# Power.net
KiCad netlist of a schematic drawn in Altium Designer
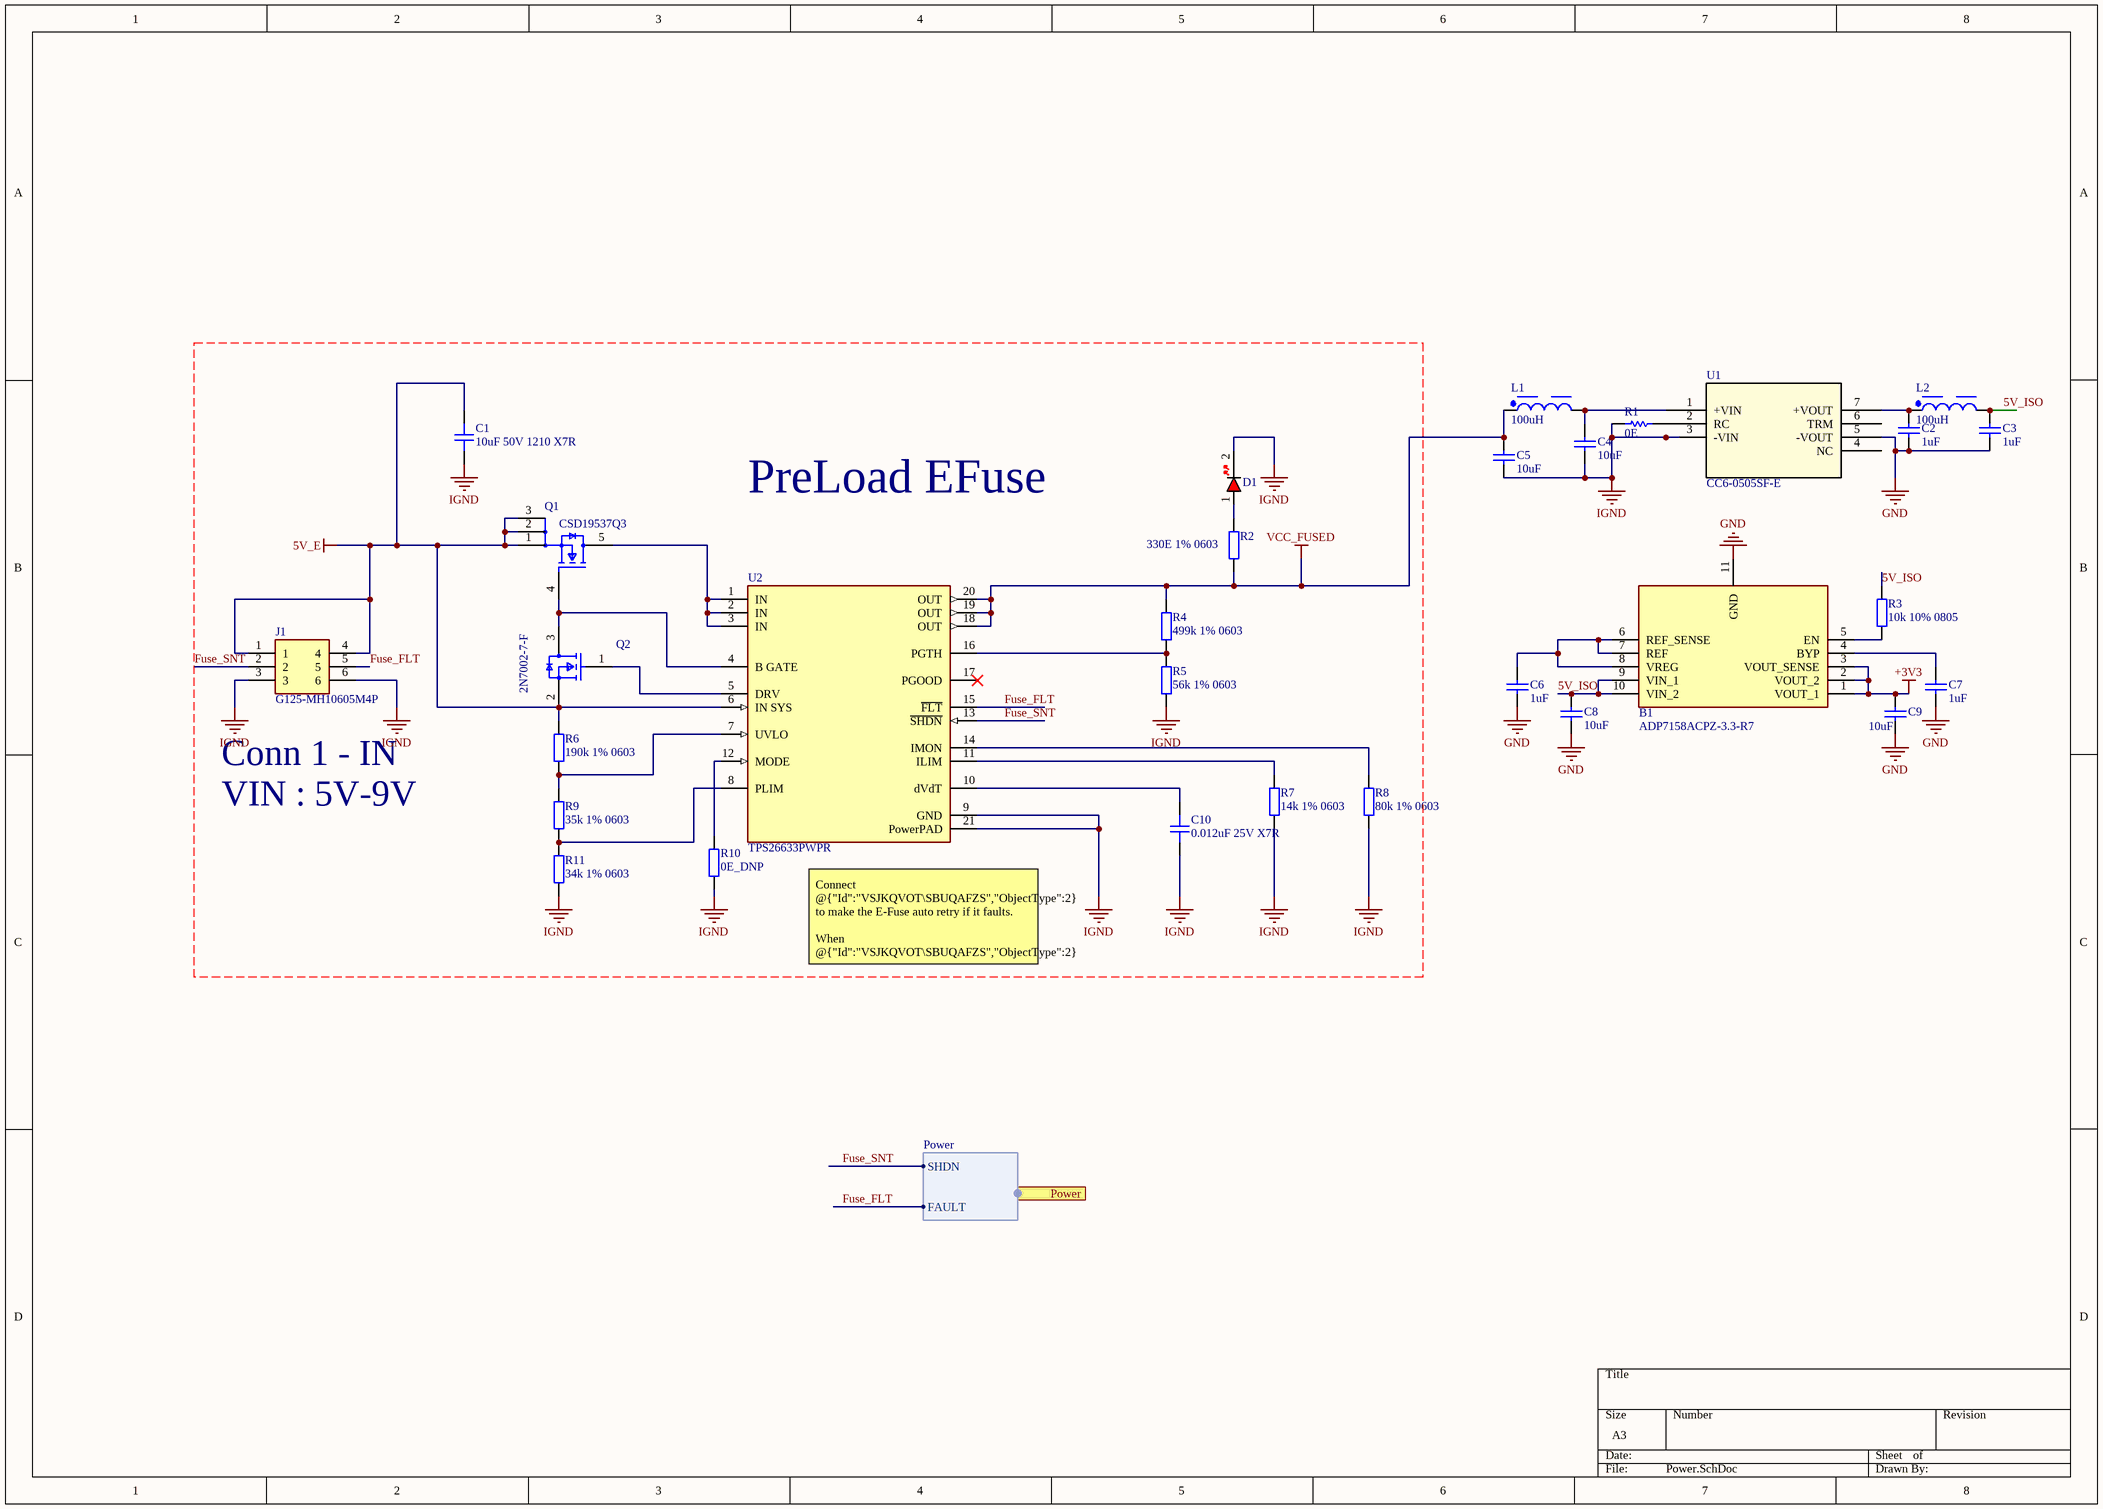
[diagram p0: Power.SchDoc]

(export (version "E")
  (design (tool "Eeschema 10.0.6"))
  (components
    (comp (ref "B1")
      (value "ADP7158ACPZ-3.3-R7")
      (footprint "LFCSP -10")
      (description "LDO Voltage Regulators 3.3/5Vin 2A Ultra Low Noise LDO Fixed")
      (fields (field (name "MOUSER PART NUMBER") "584-ADP7158ACPZ3.3R7"))
      (libsource (lib "ADP7158ACPZ-3.3-R7") (part "ADP7158ACPZ-3.3-R7"))
    )
    (comp (ref "C1")
      (value "10uF 50V 1210 X7R")
      (footprint "CAP1210S")
      (description "Capacitor SMD 1210")
      (libsource (lib "Schematic-Lib-PhilsLab") (part "CAP_1210"))
    )
    (comp (ref "C2")
      (value "1uF")
      (footprint "CAP0603S")
      (description "Capacitor")
      (fields (field (name "PUBLISHER") "Altium Limited"))
      (libsource (lib "Miscellaneous Devices") (part "CAP"))
    )
    (comp (ref "C3")
      (value "1uF")
      (footprint "CAP0603S")
      (description "Capacitor")
      (fields (field (name "PUBLISHER") "Altium Limited"))
      (libsource (lib "Miscellaneous Devices") (part "CAP"))
    )
    (comp (ref "C4")
      (value "10uF")
      (footprint "CAP0603S")
      (description "Capacitor")
      (fields (field (name "PUBLISHER") "Altium Limited"))
      (libsource (lib "Miscellaneous Devices") (part "CAP"))
    )
    (comp (ref "C5")
      (value "10uF")
      (footprint "CAP0603S")
      (description "Capacitor")
      (fields (field (name "PUBLISHER") "Altium Limited"))
      (libsource (lib "Miscellaneous Devices") (part "CAP"))
    )
    (comp (ref "C6")
      (value "1uF")
      (footprint "CAP0603S")
      (description "Capacitor")
      (fields (field (name "PUBLISHER") "Altium Limited"))
      (libsource (lib "Miscellaneous Devices") (part "CAP"))
    )
    (comp (ref "C7")
      (value "1uF")
      (footprint "CAP0603S")
      (description "Capacitor")
      (fields (field (name "PUBLISHER") "Altium Limited"))
      (libsource (lib "Miscellaneous Devices") (part "CAP"))
    )
    (comp (ref "C8")
      (value "10uF")
      (footprint "CAP0603S")
      (description "Capacitor")
      (fields (field (name "PUBLISHER") "Altium Limited"))
      (libsource (lib "Miscellaneous Devices") (part "CAP"))
    )
    (comp (ref "C9")
      (value "10uF")
      (footprint "CAP0603S")
      (description "Capacitor")
      (fields (field (name "PUBLISHER") "Altium Limited"))
      (libsource (lib "Miscellaneous Devices") (part "CAP"))
    )
    (comp (ref "C10")
      (value "0.012uF 25V X7R")
      (footprint "CAP0805S")
      (description "Capacitor SMD 0603")
      (libsource (lib "Schematic-Lib-PhilsLab") (part "CAP_0603"))
    )
    (comp (ref "D1")
      (value "RED")
      (footprint "LED 0603_RED")
      (description "LED 0603 RED SMD")
      (libsource (lib "Schematic-Lib-PhilsLab") (part "LED_0603_RED"))
    )
    (comp (ref "J1")
      (value "G125-MH10605M4P")
      (footprint "HARWIN_G125-MH10605M4P")
      (description "Connector")
      (fields (field (name "MOUSER PART NUMBER") "855-G125MH1065M4PM4P"))
      (libsource (lib "SamacSys") (part "G125-MH10605M4P"))
    )
    (comp (ref "L1")
      (value "100uH")
      (footprint "IND_SEMI_SHIELD_6.0X6.0_H4.5_SMD")
      (fields (field (name "TOLERANCE") "20%"))
      (libsource (lib "TMTC_Board") (part "CMP-1396-00036-2"))
    )
    (comp (ref "L2")
      (value "100uH")
      (footprint "IND_SEMI_SHIELD_6.0X6.0_H4.5_SMD")
      (fields (field (name "TOLERANCE") "20%"))
      (libsource (lib "TMTC_Board") (part "CMP-1396-00036-2"))
    )
    (comp (ref "Q1")
      (value "CSD19537Q3")
      (footprint "TRANS_CSD19537Q3")
      (description "MOSFET N-CH 100V 50A 8VSON")
      (libsource (lib "Miscellaneous Devices") (part "7382af88e928fdc71488234cfaaf11c"))
    )
    (comp (ref "Q2")
      (value "2N7002-7-F")
      (footprint "SOT23_3")
      (description "MOSFET N-CH 60V 115MA SOT23-3")
      (fields (field (name "VOLTAGE") "60V"))
      (libsource (lib "Miscellaneous Devices") (part "3b9c635fedb024a5347a57b145af9cc"))
    )
    (comp (ref "R1")
      (value "0E")
      (footprint "RES0402S")
      (description "Resistor")
      (fields (field (name "PUBLISHER") "Altium Limited"))
      (libsource (lib "Miscellaneous Devices") (part "res1"))
    )
    (comp (ref "R2")
      (value "330E 1% 0603")
      (footprint "RES0603S")
      (description "Resistor SMD 0603")
      (libsource (lib "Schematic-Lib-PhilsLab") (part "RES_0603"))
    )
    (comp (ref "R3")
      (value "10k 10% 0805")
      (footprint "RES0805S")
      (description "Resistor SMD 0805")
      (libsource (lib "Schematic-Lib-PhilsLab") (part "RES_0805"))
    )
    (comp (ref "R4")
      (value "499k 1% 0603")
      (footprint "RES0603S")
      (description "Resistor SMD 0603")
      (libsource (lib "Schematic-Lib-PhilsLab") (part "RES_0603"))
    )
    (comp (ref "R5")
      (value "56k 1% 0603")
      (footprint "RES0603S")
      (description "Resistor SMD 0603")
      (libsource (lib "Schematic-Lib-PhilsLab") (part "RES_0603"))
    )
    (comp (ref "R6")
      (value "190k 1% 0603")
      (footprint "RES0603S")
      (description "Resistor SMD 0603")
      (libsource (lib "Schematic-Lib-PhilsLab") (part "RES_0603"))
    )
    (comp (ref "R7")
      (value "14k 1% 0603")
      (footprint "RES0603S")
      (description "Resistor SMD 0603")
      (libsource (lib "Schematic-Lib-PhilsLab") (part "RES_0603"))
    )
    (comp (ref "R8")
      (value "80k 1% 0603")
      (footprint "RES0402S")
      (description "Resistor SMD 0603")
      (libsource (lib "Schematic-Lib-PhilsLab") (part "RES_0603"))
    )
    (comp (ref "R9")
      (value "35k 1% 0603")
      (footprint "RES0603S")
      (description "Resistor SMD 0603")
      (libsource (lib "Schematic-Lib-PhilsLab") (part "RES_0603"))
    )
    (comp (ref "R10")
      (value "0E_DNP")
      (footprint "RES0603S")
      (description "Resistor SMD 0603")
      (libsource (lib "Schematic-Lib-PhilsLab") (part "RES_0603"))
    )
    (comp (ref "R11")
      (value "34k 1% 0603")
      (footprint "RES0603S")
      (description "Resistor SMD 0603")
      (libsource (lib "Schematic-Lib-PhilsLab") (part "RES_0603"))
    )
    (comp (ref "U1")
      (value "CC6-0505SF-E")
      (footprint "CONV_CC6-0505SF-E")
      (description "No Description Available")
      (libsource (lib "CC6-0505SF-E") (part "CC6-0505SF-E"))
    )
    (comp (ref "U2")
      (value "TPS26633PWPR")
      (footprint "SOP65P640X110-21N")
      (description "4.5V - 60V 6A 29MOHM EFUSE")
      (libsource (lib "Miscellaneous Devices") (part "3aa6c8470eea581a3a5f71473fd1f1f"))
    )
  )
  (nets
    (net (code "2") (name "+3V3") (class "Default")
      (node (ref "B1") (pin "1") (pinfunction "VOUT_1_1") (pintype "passive"))
      (node (ref "B1") (pin "2") (pinfunction "VOUT_2_2") (pintype "passive"))
      (node (ref "B1") (pin "3") (pinfunction "VOUT_SENSE_3") (pintype "passive"))
      (node (ref "C9") (pin "1") (pinfunction "1_1") (pintype "passive"))
    )
    (net (code "3") (name "/5V_ISO") (class "Default")
      (node (ref "B1") (pin "10") (pinfunction "VIN_2_10") (pintype "passive"))
      (node (ref "B1") (pin "9") (pinfunction "VIN_1_9") (pintype "passive"))
      (node (ref "C3") (pin "1") (pinfunction "1_1") (pintype "passive"))
      (node (ref "C8") (pin "1") (pinfunction "1_1") (pintype "passive"))
      (node (ref "L2") (pin "2") (pinfunction "2_2") (pintype "passive"))
      (node (ref "R3") (pin "1") (pinfunction "1_1") (pintype "passive"))
    )
    (net (code "4") (name "/Fuse_FLT") (class "Default")
      (node (ref "J1") (pin "5") (pinfunction "5_5") (pintype "passive"))
      (node (ref "U2") (pin "15") (pinfunction "~{FLT}_15") (pintype "passive"))
    )
    (net (code "5") (name "/Fuse_SNT") (class "Default")
      (node (ref "J1") (pin "2") (pinfunction "2_2") (pintype "passive"))
      (node (ref "U2") (pin "13") (pinfunction "~{SHDN}_13") (pintype "input"))
    )
    (net (code "7") (name "5V_E") (class "Default")
      (node (ref "C1") (pin "2") (pinfunction "2_2") (pintype "passive"))
      (node (ref "J1") (pin "1") (pinfunction "1_1") (pintype "passive"))
      (node (ref "J1") (pin "4") (pinfunction "4_4") (pintype "passive"))
      (node (ref "Q1") (pin "1") (pinfunction "S_1") (pintype "passive"))
      (node (ref "Q1") (pin "2") (pinfunction "S_2") (pintype "passive"))
      (node (ref "Q1") (pin "3") (pinfunction "S_3") (pintype "passive"))
      (node (ref "Q2") (pin "2") (pinfunction "S_2") (pintype "passive"))
      (node (ref "R6") (pin "2") (pinfunction "2_2") (pintype "passive"))
      (node (ref "U2") (pin "6") (pinfunction "IN_SYS_6") (pintype "input"))
    )
    (net (code "8") (name "GND") (class "Default")
      (node (ref "B1") (pin "11") (pinfunction "GND_11") (pintype "passive"))
      (node (ref "C2") (pin "2") (pinfunction "2_2") (pintype "passive"))
      (node (ref "C3") (pin "2") (pinfunction "2_2") (pintype "passive"))
      (node (ref "C6") (pin "2") (pinfunction "2_2") (pintype "passive"))
      (node (ref "C7") (pin "2") (pinfunction "2_2") (pintype "passive"))
      (node (ref "C8") (pin "2") (pinfunction "2_2") (pintype "passive"))
      (node (ref "C9") (pin "2") (pinfunction "2_2") (pintype "passive"))
      (node (ref "U1") (pin "5") (pinfunction "-VOUT_5") (pintype "passive"))
    )
    (net (code "9") (name "IGND") (class "Default")
      (node (ref "C1") (pin "1") (pinfunction "1_1") (pintype "passive"))
      (node (ref "C10") (pin "1") (pinfunction "1_1") (pintype "passive"))
      (node (ref "C4") (pin "2") (pinfunction "2_2") (pintype "passive"))
      (node (ref "C5") (pin "2") (pinfunction "2_2") (pintype "passive"))
      (node (ref "D1") (pin "2") (pinfunction "K_2") (pintype "passive"))
      (node (ref "J1") (pin "3") (pinfunction "3_3") (pintype "passive"))
      (node (ref "J1") (pin "6") (pinfunction "6_6") (pintype "passive"))
      (node (ref "R1") (pin "1") (pinfunction "1_1") (pintype "passive"))
      (node (ref "R10") (pin "1") (pinfunction "1_1") (pintype "passive"))
      (node (ref "R11") (pin "1") (pinfunction "1_1") (pintype "passive"))
      (node (ref "R5") (pin "1") (pinfunction "1_1") (pintype "passive"))
      (node (ref "R7") (pin "1") (pinfunction "1_1") (pintype "passive"))
      (node (ref "R8") (pin "1") (pinfunction "1_1") (pintype "passive"))
      (node (ref "U1") (pin "3") (pinfunction "-VIN_3") (pintype "power_in"))
      (node (ref "U2") (pin "21") (pinfunction "PowerPAD_21") (pintype "power_in"))
      (node (ref "U2") (pin "9") (pinfunction "GND_9") (pintype "power_in"))
    )
    (net (code "10") (name "Net-(B1-BYP)") (class "Default")
      (node (ref "B1") (pin "4") (pinfunction "BYP_4") (pintype "passive"))
      (node (ref "C7") (pin "1") (pinfunction "1_1") (pintype "passive"))
    )
    (net (code "11") (name "Net-(B1-EN)") (class "Default")
      (node (ref "B1") (pin "5") (pinfunction "EN_5") (pintype "passive"))
      (node (ref "R3") (pin "2") (pinfunction "2_2") (pintype "passive"))
    )
    (net (code "12") (name "Net-(B1-REF)") (class "Default")
      (node (ref "B1") (pin "6") (pinfunction "REF_SENSE_6") (pintype "passive"))
      (node (ref "B1") (pin "7") (pinfunction "REF_7") (pintype "passive"))
      (node (ref "B1") (pin "8") (pinfunction "VREG_8") (pintype "passive"))
      (node (ref "C6") (pin "1") (pinfunction "1_1") (pintype "passive"))
    )
    (net (code "13") (name "Net-(D1-A)") (class "Default")
      (node (ref "D1") (pin "1") (pinfunction "A_1") (pintype "passive"))
      (node (ref "R2") (pin "2") (pinfunction "2_2") (pintype "passive"))
    )
    (net (code "14") (name "Net-(Q1-D)") (class "Default")
      (node (ref "Q1") (pin "5") (pinfunction "D_5") (pintype "passive"))
      (node (ref "U2") (pin "1") (pinfunction "IN_1") (pintype "power_in"))
      (node (ref "U2") (pin "2") (pinfunction "IN_2") (pintype "power_in"))
      (node (ref "U2") (pin "3") (pinfunction "IN_3") (pintype "power_in"))
    )
    (net (code "15") (name "Net-(Q1-G)") (class "Default")
      (node (ref "Q1") (pin "4") (pinfunction "G_4") (pintype "passive"))
      (node (ref "Q2") (pin "3") (pinfunction "D_3") (pintype "passive"))
      (node (ref "U2") (pin "4") (pinfunction "B_GATE_4") (pintype "passive"))
    )
    (net (code "16") (name "Net-(Q2-G)") (class "Default")
      (node (ref "Q2") (pin "1") (pinfunction "G_1") (pintype "passive"))
      (node (ref "U2") (pin "5") (pinfunction "DRV_5") (pintype "passive"))
    )
    (net (code "17") (name "Net-(U1-+VIN)") (class "Default")
      (node (ref "C4") (pin "1") (pinfunction "1_1") (pintype "passive"))
      (node (ref "L1") (pin "2") (pinfunction "2_2") (pintype "passive"))
      (node (ref "U1") (pin "1") (pinfunction "+VIN_1") (pintype "power_in"))
    )
    (net (code "18") (name "Net-(U1-+VOUT)") (class "Default")
      (node (ref "C2") (pin "1") (pinfunction "1_1") (pintype "passive"))
      (node (ref "L2") (pin "1") (pinfunction "1_1") (pintype "passive"))
      (node (ref "U1") (pin "7") (pinfunction "+VOUT_7") (pintype "passive"))
    )
    (net (code "19") (name "Net-(U1-RC)") (class "Default")
      (node (ref "R1") (pin "2") (pinfunction "2_2") (pintype "passive"))
      (node (ref "U1") (pin "2") (pinfunction "RC_2") (pintype "passive"))
    )
    (net (code "20") (name "Net-(U2-ILIM)") (class "Default")
      (node (ref "R7") (pin "2") (pinfunction "2_2") (pintype "passive"))
      (node (ref "U2") (pin "11") (pinfunction "ILIM_11") (pintype "passive"))
    )
    (net (code "21") (name "Net-(U2-IMON)") (class "Default")
      (node (ref "R8") (pin "2") (pinfunction "2_2") (pintype "passive"))
      (node (ref "U2") (pin "14") (pinfunction "IMON_14") (pintype "passive"))
    )
    (net (code "22") (name "Net-(U2-MODE)") (class "Default")
      (node (ref "R10") (pin "2") (pinfunction "2_2") (pintype "passive"))
      (node (ref "U2") (pin "12") (pinfunction "MODE_12") (pintype "input"))
    )
    (net (code "23") (name "Net-(U2-PGTH)") (class "Default")
      (node (ref "R4") (pin "1") (pinfunction "1_1") (pintype "passive"))
      (node (ref "R5") (pin "2") (pinfunction "2_2") (pintype "passive"))
      (node (ref "U2") (pin "16") (pinfunction "PGTH_16") (pintype "passive"))
    )
    (net (code "24") (name "Net-(U2-PLIM)") (class "Default")
      (node (ref "R11") (pin "2") (pinfunction "2_2") (pintype "passive"))
      (node (ref "R9") (pin "1") (pinfunction "1_1") (pintype "passive"))
      (node (ref "U2") (pin "8") (pinfunction "PLIM_8") (pintype "passive"))
    )
    (net (code "25") (name "Net-(U2-UVLO)") (class "Default")
      (node (ref "R6") (pin "1") (pinfunction "1_1") (pintype "passive"))
      (node (ref "R9") (pin "2") (pinfunction "2_2") (pintype "passive"))
      (node (ref "U2") (pin "7") (pinfunction "UVLO_7") (pintype "input"))
    )
    (net (code "26") (name "Net-(U2-dVdT)") (class "Default")
      (node (ref "C10") (pin "2") (pinfunction "2_2") (pintype "passive"))
      (node (ref "U2") (pin "10") (pinfunction "dVdT_10") (pintype "passive"))
    )
    (net (code "27") (name "VCC_FUSED") (class "Default")
      (node (ref "C5") (pin "1") (pinfunction "1_1") (pintype "passive"))
      (node (ref "L1") (pin "1") (pinfunction "1_1") (pintype "passive"))
      (node (ref "R2") (pin "1") (pinfunction "1_1") (pintype "passive"))
      (node (ref "R4") (pin "2") (pinfunction "2_2") (pintype "passive"))
      (node (ref "U2") (pin "18") (pinfunction "OUT_18") (pintype "output"))
      (node (ref "U2") (pin "19") (pinfunction "OUT_19") (pintype "output"))
      (node (ref "U2") (pin "20") (pinfunction "OUT_20") (pintype "output"))
    )
    (net (code "28") (name "unconnected-(U1-NC-Pad4)") (class "Default")
      (node (ref "U1") (pin "4") (pinfunction "NC_4") (pintype "passive"))
    )
    (net (code "29") (name "unconnected-(U1-TRM-Pad6)") (class "Default")
      (node (ref "U1") (pin "6") (pinfunction "TRM_6") (pintype "passive"))
    )
    (net (code "30") (name "unconnected-(U2-PGOOD-Pad17)") (class "Default")
      (node (ref "U2") (pin "17") (pinfunction "PGOOD_17") (pintype "open_collector+no_connect"))
    )
  )
)
